# Button_Sequencer.net
KiCad netlist of a schematic drawn in EAGLE
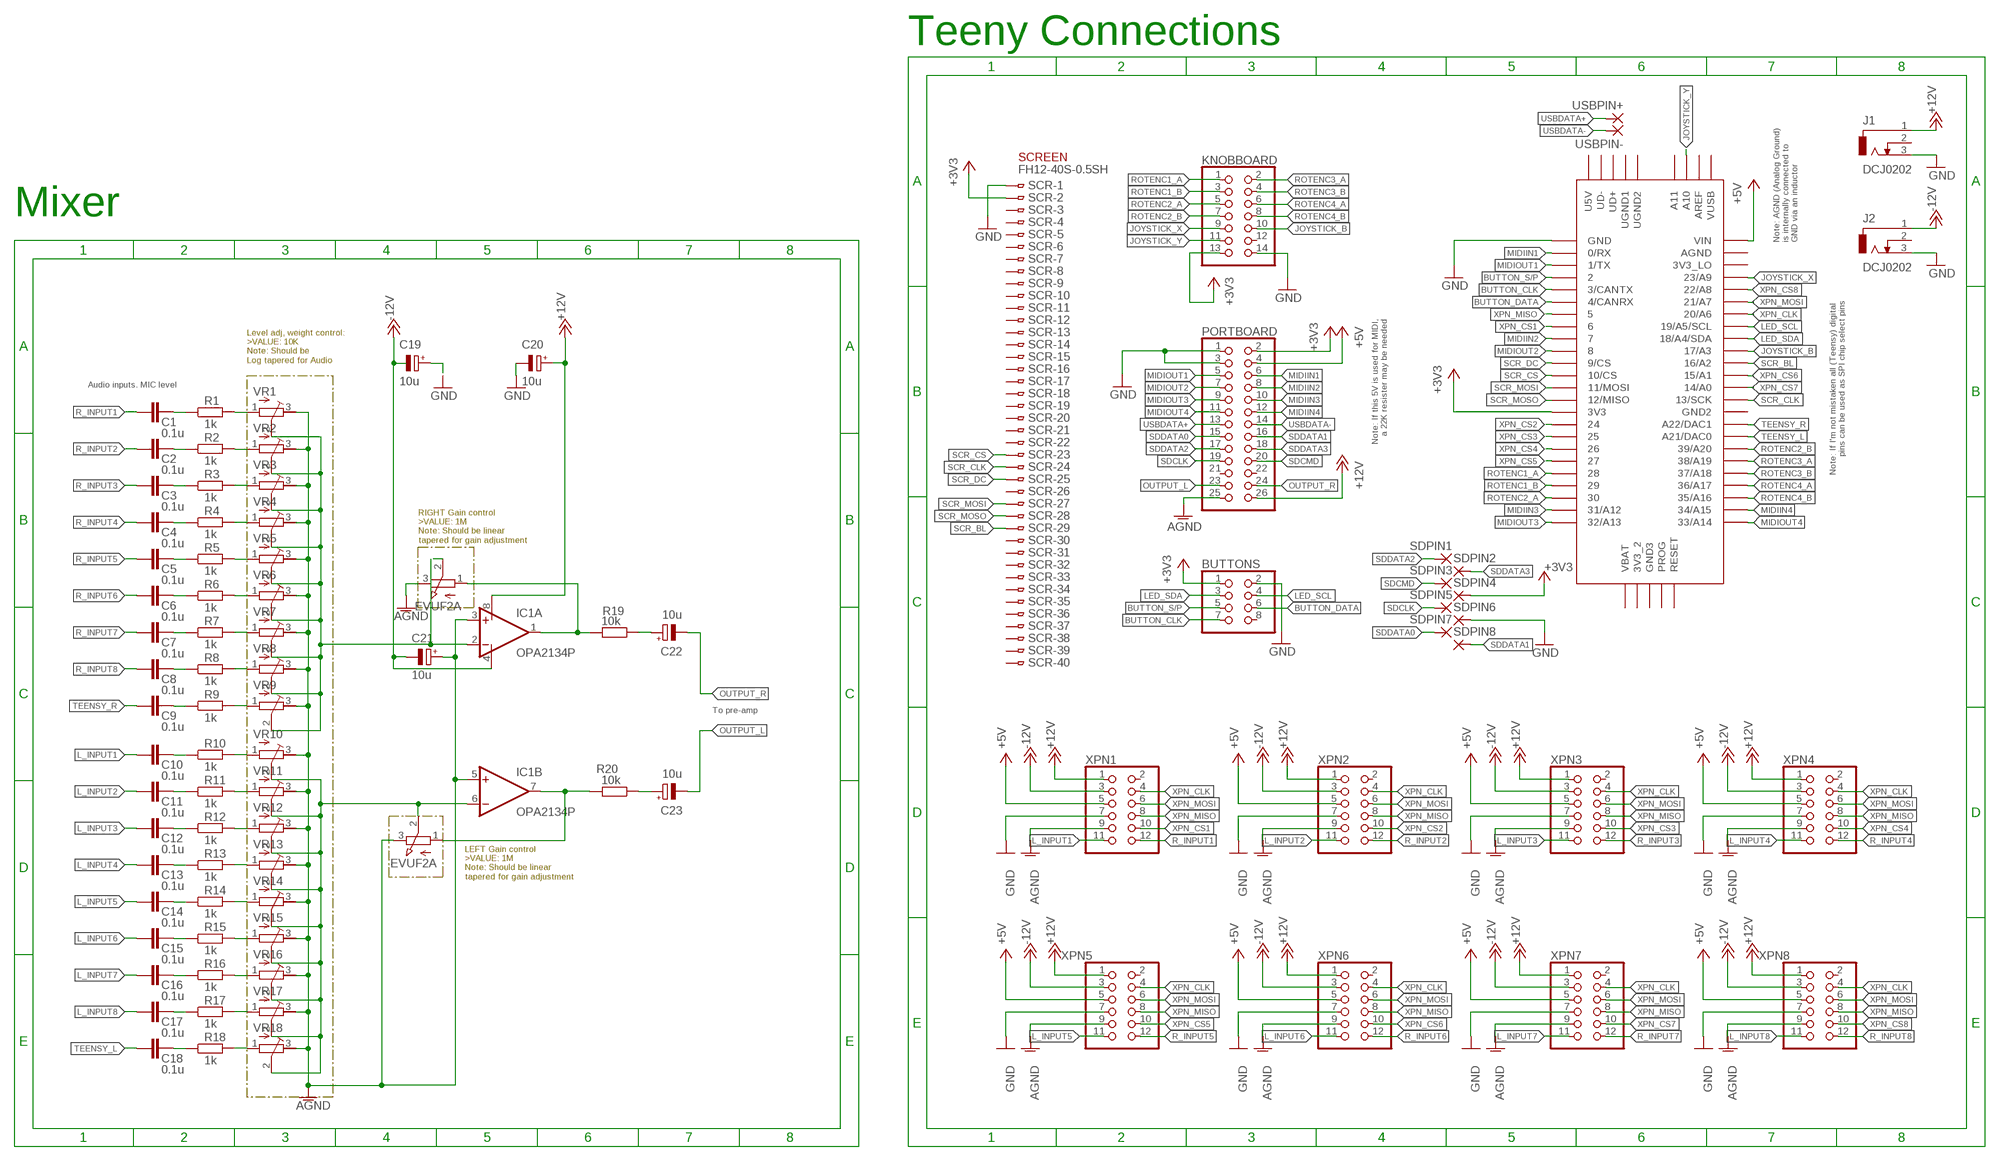
[diagram p0: schematic, sheet 1]

(export (version "E")
  (design (tool "Eeschema 10.0.6"))
  (components
    (comp (ref "BUTTONS")
      (value "PINHD-2X4")
      (footprint "eagle-import:2X04")
      (libsource (lib "eagle-import") (part "PINHD-2X4"))
    )
    (comp (ref "C1")
      (value "0.1u")
      (footprint "eagle-import:C025-030X050")
      (libsource (lib "eagle-import") (part "C-EU025-030X050"))
    )
    (comp (ref "C2")
      (value "0.1u")
      (footprint "eagle-import:C025-030X050")
      (libsource (lib "eagle-import") (part "C-EU025-030X050"))
    )
    (comp (ref "C3")
      (value "0.1u")
      (footprint "eagle-import:C025-030X050")
      (libsource (lib "eagle-import") (part "C-EU025-030X050"))
    )
    (comp (ref "C4")
      (value "0.1u")
      (footprint "eagle-import:C025-030X050")
      (libsource (lib "eagle-import") (part "C-EU025-030X050"))
    )
    (comp (ref "C5")
      (value "0.1u")
      (footprint "eagle-import:C025-030X050")
      (libsource (lib "eagle-import") (part "C-EU025-030X050"))
    )
    (comp (ref "C6")
      (value "0.1u")
      (footprint "eagle-import:C025-030X050")
      (libsource (lib "eagle-import") (part "C-EU025-030X050"))
    )
    (comp (ref "C7")
      (value "0.1u")
      (footprint "eagle-import:C025-030X050")
      (libsource (lib "eagle-import") (part "C-EU025-030X050"))
    )
    (comp (ref "C8")
      (value "0.1u")
      (footprint "eagle-import:C025-030X050")
      (libsource (lib "eagle-import") (part "C-EU025-030X050"))
    )
    (comp (ref "C9")
      (value "0.1u")
      (footprint "eagle-import:C025-030X050")
      (libsource (lib "eagle-import") (part "C-EU025-030X050"))
    )
    (comp (ref "C10")
      (value "0.1u")
      (footprint "eagle-import:C025-030X050")
      (libsource (lib "eagle-import") (part "C-EU025-030X050"))
    )
    (comp (ref "C11")
      (value "0.1u")
      (footprint "eagle-import:C025-030X050")
      (libsource (lib "eagle-import") (part "C-EU025-030X050"))
    )
    (comp (ref "C12")
      (value "0.1u")
      (footprint "eagle-import:C025-030X050")
      (libsource (lib "eagle-import") (part "C-EU025-030X050"))
    )
    (comp (ref "C13")
      (value "0.1u")
      (footprint "eagle-import:C025-030X050")
      (libsource (lib "eagle-import") (part "C-EU025-030X050"))
    )
    (comp (ref "C14")
      (value "0.1u")
      (footprint "eagle-import:C025-030X050")
      (libsource (lib "eagle-import") (part "C-EU025-030X050"))
    )
    (comp (ref "C15")
      (value "0.1u")
      (footprint "eagle-import:C025-030X050")
      (libsource (lib "eagle-import") (part "C-EU025-030X050"))
    )
    (comp (ref "C16")
      (value "0.1u")
      (footprint "eagle-import:C025-030X050")
      (libsource (lib "eagle-import") (part "C-EU025-030X050"))
    )
    (comp (ref "C17")
      (value "0.1u")
      (footprint "eagle-import:C025-030X050")
      (libsource (lib "eagle-import") (part "C-EU025-030X050"))
    )
    (comp (ref "C18")
      (value "0.1u")
      (footprint "eagle-import:C025-030X050")
      (libsource (lib "eagle-import") (part "C-EU025-030X050"))
    )
    (comp (ref "C19")
      (value "10u")
      (footprint "eagle-import:E5-10,5")
      (libsource (lib "eagle-import") (part "CPOL-EUE5-10.5"))
    )
    (comp (ref "C20")
      (value "10u")
      (footprint "eagle-import:E5-10,5")
      (libsource (lib "eagle-import") (part "CPOL-EUE5-10.5"))
    )
    (comp (ref "C21")
      (value "10u")
      (footprint "eagle-import:E5-10,5")
      (libsource (lib "eagle-import") (part "CPOL-EUE5-10.5"))
    )
    (comp (ref "C22")
      (value "10u")
      (footprint "eagle-import:E5-10,5")
      (libsource (lib "eagle-import") (part "CPOL-EUE5-10.5"))
    )
    (comp (ref "C23")
      (value "10u")
      (footprint "eagle-import:E5-10,5")
      (libsource (lib "eagle-import") (part "CPOL-EUE5-10.5"))
    )
    (comp (ref "IC1")
      (value "OPA2134P")
      (footprint "eagle-import:DIL08")
      (libsource (lib "eagle-import") (part "OPA2134P"))
    )
    (comp (ref "J1")
      (value "DCJ0202")
      (footprint "eagle-import:DCJ0202")
      (libsource (lib "eagle-import") (part "DCJ0202"))
    )
    (comp (ref "J2")
      (value "DCJ0202")
      (footprint "eagle-import:DCJ0202")
      (libsource (lib "eagle-import") (part "DCJ0202"))
    )
    (comp (ref "KNOBBOARD")
      (value "PINHD-2X7")
      (footprint "eagle-import:2X07")
      (libsource (lib "eagle-import") (part "PINHD-2X7"))
    )
    (comp (ref "PORTBOARD")
      (value "PINHD-2X13")
      (footprint "eagle-import:2X13")
      (libsource (lib "eagle-import") (part "PINHD-2X13"))
    )
    (comp (ref "R1")
      (value "1k")
      (footprint "eagle-import:R0805")
      (libsource (lib "eagle-import") (part "R-EU_R0805"))
    )
    (comp (ref "R2")
      (value "1k")
      (footprint "eagle-import:R0805")
      (libsource (lib "eagle-import") (part "R-EU_R0805"))
    )
    (comp (ref "R3")
      (value "1k")
      (footprint "eagle-import:R0805")
      (libsource (lib "eagle-import") (part "R-EU_R0805"))
    )
    (comp (ref "R4")
      (value "1k")
      (footprint "eagle-import:R0805")
      (libsource (lib "eagle-import") (part "R-EU_R0805"))
    )
    (comp (ref "R5")
      (value "1k")
      (footprint "eagle-import:R0805")
      (libsource (lib "eagle-import") (part "R-EU_R0805"))
    )
    (comp (ref "R6")
      (value "1k")
      (footprint "eagle-import:R0805")
      (libsource (lib "eagle-import") (part "R-EU_R0805"))
    )
    (comp (ref "R7")
      (value "1k")
      (footprint "eagle-import:R0805")
      (libsource (lib "eagle-import") (part "R-EU_R0805"))
    )
    (comp (ref "R8")
      (value "1k")
      (footprint "eagle-import:R0805")
      (libsource (lib "eagle-import") (part "R-EU_R0805"))
    )
    (comp (ref "R9")
      (value "1k")
      (footprint "eagle-import:R0805")
      (libsource (lib "eagle-import") (part "R-EU_R0805"))
    )
    (comp (ref "R10")
      (value "1k")
      (footprint "eagle-import:R0805")
      (libsource (lib "eagle-import") (part "R-EU_R0805"))
    )
    (comp (ref "R11")
      (value "1k")
      (footprint "eagle-import:R0805")
      (libsource (lib "eagle-import") (part "R-EU_R0805"))
    )
    (comp (ref "R12")
      (value "1k")
      (footprint "eagle-import:R0805")
      (libsource (lib "eagle-import") (part "R-EU_R0805"))
    )
    (comp (ref "R13")
      (value "1k")
      (footprint "eagle-import:R0805")
      (libsource (lib "eagle-import") (part "R-EU_R0805"))
    )
    (comp (ref "R14")
      (value "1k")
      (footprint "eagle-import:R0805")
      (libsource (lib "eagle-import") (part "R-EU_R0805"))
    )
    (comp (ref "R15")
      (value "1k")
      (footprint "eagle-import:R0805")
      (libsource (lib "eagle-import") (part "R-EU_R0805"))
    )
    (comp (ref "R16")
      (value "1k")
      (footprint "eagle-import:R0805")
      (libsource (lib "eagle-import") (part "R-EU_R0805"))
    )
    (comp (ref "R17")
      (value "1k")
      (footprint "eagle-import:R0805")
      (libsource (lib "eagle-import") (part "R-EU_R0805"))
    )
    (comp (ref "R18")
      (value "1k")
      (footprint "eagle-import:R0805")
      (libsource (lib "eagle-import") (part "R-EU_R0805"))
    )
    (comp (ref "R19")
      (value "10k")
      (footprint "eagle-import:R0805")
      (libsource (lib "eagle-import") (part "R-EU_R0805"))
    )
    (comp (ref "R20")
      (value "10k")
      (footprint "eagle-import:R0805")
      (libsource (lib "eagle-import") (part "R-EU_R0805"))
    )
    (comp (ref "SCR")
      (value "FH12-40S-0.5SH")
      (footprint "eagle-import:FH12-40S-0.5SH")
      (fields (field (name "MPN") "FH12-40S-0.5SH(55)"))
      (libsource (lib "eagle-import") (part "FH12-40S-0.5SH"))
    )
    (comp (ref "SDPIN1")
      (value "1,6/0,8")
      (footprint "eagle-import:1,6_0,8")
      (libsource (lib "eagle-import") (part "1,6/0,8"))
    )
    (comp (ref "SDPIN2")
      (value "1,6/0,8")
      (footprint "eagle-import:1,6_0,8")
      (libsource (lib "eagle-import") (part "1,6/0,8"))
    )
    (comp (ref "SDPIN3")
      (value "1,6/0,8")
      (footprint "eagle-import:1,6_0,8")
      (libsource (lib "eagle-import") (part "1,6/0,8"))
    )
    (comp (ref "SDPIN4")
      (value "1,6/0,8")
      (footprint "eagle-import:1,6_0,8")
      (libsource (lib "eagle-import") (part "1,6/0,8"))
    )
    (comp (ref "SDPIN5")
      (value "1,6/0,8")
      (footprint "eagle-import:1,6_0,8")
      (libsource (lib "eagle-import") (part "1,6/0,8"))
    )
    (comp (ref "SDPIN6")
      (value "1,6/0,8")
      (footprint "eagle-import:1,6_0,8")
      (libsource (lib "eagle-import") (part "1,6/0,8"))
    )
    (comp (ref "SDPIN7")
      (value "1,6/0,8")
      (footprint "eagle-import:1,6_0,8")
      (libsource (lib "eagle-import") (part "1,6/0,8"))
    )
    (comp (ref "SDPIN8")
      (value "1,6/0,8")
      (footprint "eagle-import:1,6_0,8")
      (libsource (lib "eagle-import") (part "1,6/0,8"))
    )
    (comp (ref "TEENSY_3.6")
      (value "TEENSY_3.5/3.6")
      (footprint "eagle-import:TEENSY_3.5_3.6")
      (libsource (lib "eagle-import") (part "TEENSY_3.5/3.6"))
    )
    (comp (ref "USBPIN+")
      (value "1,6/0,8")
      (footprint "eagle-import:1,6_0,8")
      (libsource (lib "eagle-import") (part "1,6/0,8"))
    )
    (comp (ref "USBPIN-")
      (value "1,6/0,8")
      (footprint "eagle-import:1,6_0,8")
      (libsource (lib "eagle-import") (part "1,6/0,8"))
    )
    (comp (ref "VR1")
      (value "R-TRIMM3339P")
      (footprint "eagle-import:RTRIM3339P")
      (libsource (lib "eagle-import") (part "R-TRIMM3339P"))
    )
    (comp (ref "VR2")
      (value "R-TRIMM3339P")
      (footprint "eagle-import:RTRIM3339P")
      (libsource (lib "eagle-import") (part "R-TRIMM3339P"))
    )
    (comp (ref "VR3")
      (value "R-TRIMM3339P")
      (footprint "eagle-import:RTRIM3339P")
      (libsource (lib "eagle-import") (part "R-TRIMM3339P"))
    )
    (comp (ref "VR4")
      (value "R-TRIMM3339P")
      (footprint "eagle-import:RTRIM3339P")
      (libsource (lib "eagle-import") (part "R-TRIMM3339P"))
    )
    (comp (ref "VR5")
      (value "R-TRIMM3339P")
      (footprint "eagle-import:RTRIM3339P")
      (libsource (lib "eagle-import") (part "R-TRIMM3339P"))
    )
    (comp (ref "VR6")
      (value "R-TRIMM3339P")
      (footprint "eagle-import:RTRIM3339P")
      (libsource (lib "eagle-import") (part "R-TRIMM3339P"))
    )
    (comp (ref "VR7")
      (value "R-TRIMM3339P")
      (footprint "eagle-import:RTRIM3339P")
      (libsource (lib "eagle-import") (part "R-TRIMM3339P"))
    )
    (comp (ref "VR8")
      (value "R-TRIMM3339P")
      (footprint "eagle-import:RTRIM3339P")
      (libsource (lib "eagle-import") (part "R-TRIMM3339P"))
    )
    (comp (ref "VR9")
      (value "R-TRIMM3339P")
      (footprint "eagle-import:RTRIM3339P")
      (libsource (lib "eagle-import") (part "R-TRIMM3339P"))
    )
    (comp (ref "VR10")
      (value "R-TRIMM3339P")
      (footprint "eagle-import:RTRIM3339P")
      (libsource (lib "eagle-import") (part "R-TRIMM3339P"))
    )
    (comp (ref "VR11")
      (value "R-TRIMM3339P")
      (footprint "eagle-import:RTRIM3339P")
      (libsource (lib "eagle-import") (part "R-TRIMM3339P"))
    )
    (comp (ref "VR12")
      (value "R-TRIMM3339P")
      (footprint "eagle-import:RTRIM3339P")
      (libsource (lib "eagle-import") (part "R-TRIMM3339P"))
    )
    (comp (ref "VR13")
      (value "R-TRIMM3339P")
      (footprint "eagle-import:RTRIM3339P")
      (libsource (lib "eagle-import") (part "R-TRIMM3339P"))
    )
    (comp (ref "VR14")
      (value "R-TRIMM3339P")
      (footprint "eagle-import:RTRIM3339P")
      (libsource (lib "eagle-import") (part "R-TRIMM3339P"))
    )
    (comp (ref "VR15")
      (value "R-TRIMM3339P")
      (footprint "eagle-import:RTRIM3339P")
      (libsource (lib "eagle-import") (part "R-TRIMM3339P"))
    )
    (comp (ref "VR16")
      (value "R-TRIMM3339P")
      (footprint "eagle-import:RTRIM3339P")
      (libsource (lib "eagle-import") (part "R-TRIMM3339P"))
    )
    (comp (ref "VR17")
      (value "R-TRIMM3339P")
      (footprint "eagle-import:RTRIM3339P")
      (libsource (lib "eagle-import") (part "R-TRIMM3339P"))
    )
    (comp (ref "VR18")
      (value "R-TRIMM3339P")
      (footprint "eagle-import:RTRIM3339P")
      (libsource (lib "eagle-import") (part "R-TRIMM3339P"))
    )
    (comp (ref "VR19")
      (value "EVUF2A")
      (footprint "eagle-import:EVUF")
      (libsource (lib "eagle-import") (part "EVUAF2"))
    )
    (comp (ref "VR20")
      (value "EVUF2A")
      (footprint "eagle-import:EVUF")
      (libsource (lib "eagle-import") (part "EVUAF2"))
    )
    (comp (ref "XPN1")
      (value "PINHD-2X6")
      (footprint "eagle-import:2X06")
      (libsource (lib "eagle-import") (part "PINHD-2X6"))
    )
    (comp (ref "XPN2")
      (value "PINHD-2X6")
      (footprint "eagle-import:2X06")
      (libsource (lib "eagle-import") (part "PINHD-2X6"))
    )
    (comp (ref "XPN3")
      (value "PINHD-2X6")
      (footprint "eagle-import:2X06")
      (libsource (lib "eagle-import") (part "PINHD-2X6"))
    )
    (comp (ref "XPN4")
      (value "PINHD-2X6")
      (footprint "eagle-import:2X06")
      (libsource (lib "eagle-import") (part "PINHD-2X6"))
    )
    (comp (ref "XPN5")
      (value "PINHD-2X6")
      (footprint "eagle-import:2X06")
      (libsource (lib "eagle-import") (part "PINHD-2X6"))
    )
    (comp (ref "XPN6")
      (value "PINHD-2X6")
      (footprint "eagle-import:2X06")
      (libsource (lib "eagle-import") (part "PINHD-2X6"))
    )
    (comp (ref "XPN7")
      (value "PINHD-2X6")
      (footprint "eagle-import:2X06")
      (libsource (lib "eagle-import") (part "PINHD-2X6"))
    )
    (comp (ref "XPN8")
      (value "PINHD-2X6")
      (footprint "eagle-import:2X06")
      (libsource (lib "eagle-import") (part "PINHD-2X6"))
    )
  )
  (nets
    (net (code "1") (name "+3V3") (class "Default")
      (node (ref "BUTTONS") (pin "1") (pinfunction "1_1") (pintype "passive"))
      (node (ref "KNOBBOARD") (pin "13") (pinfunction "13_13") (pintype "passive"))
      (node (ref "PORTBOARD") (pin "2") (pinfunction "2_2") (pintype "passive"))
      (node (ref "SCR") (pin "2") (pinfunction "1_2") (pintype "passive"))
      (node (ref "SDPIN4") (pin "1") (pinfunction "P_1") (pintype "passive"))
      (node (ref "TEENSY_3.6") (pin "3V3") (pinfunction "3V3_3V3") (pintype "bidirectional"))
    )
    (net (code "2") (name "+5V") (class "Default")
      (node (ref "PORTBOARD") (pin "4") (pinfunction "4_4") (pintype "passive"))
      (node (ref "TEENSY_3.6") (pin "VIN") (pinfunction "VIN_VIN") (pintype "bidirectional"))
      (node (ref "XPN1") (pin "5") (pinfunction "5_5") (pintype "passive"))
      (node (ref "XPN2") (pin "5") (pinfunction "5_5") (pintype "passive"))
      (node (ref "XPN3") (pin "5") (pinfunction "5_5") (pintype "passive"))
      (node (ref "XPN4") (pin "5") (pinfunction "5_5") (pintype "passive"))
      (node (ref "XPN5") (pin "5") (pinfunction "5_5") (pintype "passive"))
      (node (ref "XPN6") (pin "5") (pinfunction "5_5") (pintype "passive"))
      (node (ref "XPN7") (pin "5") (pinfunction "5_5") (pintype "passive"))
      (node (ref "XPN8") (pin "5") (pinfunction "5_5") (pintype "passive"))
    )
    (net (code "3") (name "+12V") (class "Default")
      (node (ref "C20") (pin "+") (pinfunction "+_+") (pintype "passive"))
      (node (ref "IC1") (pin "8") (pinfunction "V+_8") (pintype "power_in"))
      (node (ref "J1") (pin "1") (pinfunction "1_1") (pintype "passive"))
      (node (ref "PORTBOARD") (pin "26") (pinfunction "26_26") (pintype "passive"))
      (node (ref "XPN1") (pin "1") (pinfunction "1_1") (pintype "passive"))
      (node (ref "XPN2") (pin "1") (pinfunction "1_1") (pintype "passive"))
      (node (ref "XPN3") (pin "1") (pinfunction "1_1") (pintype "passive"))
      (node (ref "XPN4") (pin "1") (pinfunction "1_1") (pintype "passive"))
      (node (ref "XPN5") (pin "1") (pinfunction "1_1") (pintype "passive"))
      (node (ref "XPN6") (pin "1") (pinfunction "1_1") (pintype "passive"))
      (node (ref "XPN7") (pin "1") (pinfunction "1_1") (pintype "passive"))
      (node (ref "XPN8") (pin "1") (pinfunction "1_1") (pintype "passive"))
    )
    (net (code "4") (name "-12V") (class "Default")
      (node (ref "C19") (pin "-") (pinfunction "-_-") (pintype "passive"))
      (node (ref "C21") (pin "-") (pinfunction "-_-") (pintype "passive"))
      (node (ref "IC1") (pin "4") (pinfunction "V-_4") (pintype "power_in"))
      (node (ref "J2") (pin "1") (pinfunction "1_1") (pintype "passive"))
      (node (ref "XPN1") (pin "3") (pinfunction "3_3") (pintype "passive"))
      (node (ref "XPN2") (pin "3") (pinfunction "3_3") (pintype "passive"))
      (node (ref "XPN3") (pin "3") (pinfunction "3_3") (pintype "passive"))
      (node (ref "XPN4") (pin "3") (pinfunction "3_3") (pintype "passive"))
      (node (ref "XPN5") (pin "3") (pinfunction "3_3") (pintype "passive"))
      (node (ref "XPN6") (pin "3") (pinfunction "3_3") (pintype "passive"))
      (node (ref "XPN7") (pin "3") (pinfunction "3_3") (pintype "passive"))
      (node (ref "XPN8") (pin "3") (pinfunction "3_3") (pintype "passive"))
    )
    (net (code "5") (name "AGND") (class "Default")
      (node (ref "C21") (pin "+") (pinfunction "+_+") (pintype "passive"))
      (node (ref "IC1") (pin "3") (pinfunction "+IN_3") (pintype "input"))
      (node (ref "IC1") (pin "5") (pinfunction "+IN_5") (pintype "input"))
      (node (ref "PORTBOARD") (pin "25") (pinfunction "25_25") (pintype "passive"))
      (node (ref "VR1") (pin "3") (pinfunction "E_3") (pintype "passive"))
      (node (ref "VR10") (pin "3") (pinfunction "E_3") (pintype "passive"))
      (node (ref "VR11") (pin "3") (pinfunction "E_3") (pintype "passive"))
      (node (ref "VR12") (pin "3") (pinfunction "E_3") (pintype "passive"))
      (node (ref "VR13") (pin "3") (pinfunction "E_3") (pintype "passive"))
      (node (ref "VR14") (pin "3") (pinfunction "E_3") (pintype "passive"))
      (node (ref "VR15") (pin "3") (pinfunction "E_3") (pintype "passive"))
      (node (ref "VR16") (pin "3") (pinfunction "E_3") (pintype "passive"))
      (node (ref "VR17") (pin "3") (pinfunction "E_3") (pintype "passive"))
      (node (ref "VR18") (pin "3") (pinfunction "E_3") (pintype "passive"))
      (node (ref "VR19") (pin "3") (pinfunction "E_3") (pintype "passive"))
      (node (ref "VR2") (pin "3") (pinfunction "E_3") (pintype "passive"))
      (node (ref "VR20") (pin "3") (pinfunction "E_3") (pintype "passive"))
      (node (ref "VR3") (pin "3") (pinfunction "E_3") (pintype "passive"))
      (node (ref "VR4") (pin "3") (pinfunction "E_3") (pintype "passive"))
      (node (ref "VR5") (pin "3") (pinfunction "E_3") (pintype "passive"))
      (node (ref "VR6") (pin "3") (pinfunction "E_3") (pintype "passive"))
      (node (ref "VR7") (pin "3") (pinfunction "E_3") (pintype "passive"))
      (node (ref "VR8") (pin "3") (pinfunction "E_3") (pintype "passive"))
      (node (ref "VR9") (pin "3") (pinfunction "E_3") (pintype "passive"))
      (node (ref "XPN1") (pin "9") (pinfunction "9_9") (pintype "passive"))
      (node (ref "XPN2") (pin "9") (pinfunction "9_9") (pintype "passive"))
      (node (ref "XPN3") (pin "9") (pinfunction "9_9") (pintype "passive"))
      (node (ref "XPN4") (pin "9") (pinfunction "9_9") (pintype "passive"))
      (node (ref "XPN5") (pin "9") (pinfunction "9_9") (pintype "passive"))
      (node (ref "XPN6") (pin "9") (pinfunction "9_9") (pintype "passive"))
      (node (ref "XPN7") (pin "9") (pinfunction "9_9") (pintype "passive"))
      (node (ref "XPN8") (pin "9") (pinfunction "9_9") (pintype "passive"))
    )
    (net (code "6") (name "BUTTON_CLK") (class "Default")
      (node (ref "BUTTONS") (pin "7") (pinfunction "7_7") (pintype "passive"))
      (node (ref "TEENSY_3.6") (pin "3/CANTX") (pinfunction "3/CANTX_3/CANTX") (pintype "bidirectional"))
    )
    (net (code "7") (name "BUTTON_DATA") (class "Default")
      (node (ref "BUTTONS") (pin "6") (pinfunction "6_6") (pintype "passive"))
      (node (ref "TEENSY_3.6") (pin "4/CANRX") (pinfunction "4/CANRX_4/CANRX") (pintype "bidirectional"))
    )
    (net (code "8") (name "BUTTON_S{slash}P") (class "Default")
      (node (ref "BUTTONS") (pin "5") (pinfunction "5_5") (pintype "passive"))
      (node (ref "TEENSY_3.6") (pin "2") (pinfunction "2_2") (pintype "bidirectional"))
    )
    (net (code "9") (name "GND") (class "Default")
      (node (ref "BUTTONS") (pin "2") (pinfunction "2_2") (pintype "passive"))
      (node (ref "C19") (pin "+") (pinfunction "+_+") (pintype "passive"))
      (node (ref "C20") (pin "-") (pinfunction "-_-") (pintype "passive"))
      (node (ref "J1") (pin "3") (pinfunction "3_3") (pintype "passive"))
      (node (ref "J2") (pin "3") (pinfunction "3_3") (pintype "passive"))
      (node (ref "KNOBBOARD") (pin "14") (pinfunction "14_14") (pintype "passive"))
      (node (ref "PORTBOARD") (pin "1") (pinfunction "1_1") (pintype "passive"))
      (node (ref "PORTBOARD") (pin "3") (pinfunction "3_3") (pintype "passive"))
      (node (ref "SCR") (pin "1") (pinfunction "1_1") (pintype "passive"))
      (node (ref "SDPIN6") (pin "1") (pinfunction "P_1") (pintype "passive"))
      (node (ref "TEENSY_3.6") (pin "GND") (pinfunction "GND_GND") (pintype "bidirectional"))
      (node (ref "XPN1") (pin "7") (pinfunction "7_7") (pintype "passive"))
      (node (ref "XPN2") (pin "7") (pinfunction "7_7") (pintype "passive"))
      (node (ref "XPN3") (pin "7") (pinfunction "7_7") (pintype "passive"))
      (node (ref "XPN4") (pin "7") (pinfunction "7_7") (pintype "passive"))
      (node (ref "XPN5") (pin "7") (pinfunction "7_7") (pintype "passive"))
      (node (ref "XPN6") (pin "7") (pinfunction "7_7") (pintype "passive"))
      (node (ref "XPN7") (pin "7") (pinfunction "7_7") (pintype "passive"))
      (node (ref "XPN8") (pin "7") (pinfunction "7_7") (pintype "passive"))
    )
    (net (code "10") (name "JOYSTICK_B") (class "Default")
      (node (ref "KNOBBOARD") (pin "10") (pinfunction "10_10") (pintype "passive"))
      (node (ref "TEENSY_3.6") (pin "17/A3") (pinfunction "17/A3_17/A3") (pintype "bidirectional"))
    )
    (net (code "11") (name "JOYSTICK_X") (class "Default")
      (node (ref "KNOBBOARD") (pin "9") (pinfunction "9_9") (pintype "passive"))
      (node (ref "TEENSY_3.6") (pin "23/A9") (pinfunction "23/A9_23/A9") (pintype "bidirectional"))
    )
    (net (code "12") (name "JOYSTICK_Y") (class "Default")
      (node (ref "KNOBBOARD") (pin "11") (pinfunction "11_11") (pintype "passive"))
      (node (ref "TEENSY_3.6") (pin "A10") (pinfunction "A10_A10") (pintype "bidirectional"))
    )
    (net (code "13") (name "LED_SCL") (class "Default")
      (node (ref "BUTTONS") (pin "4") (pinfunction "4_4") (pintype "passive"))
      (node (ref "TEENSY_3.6") (pin "19/A5/SCL") (pinfunction "19/A5/SCL_19/A5/SCL") (pintype "bidirectional"))
    )
    (net (code "14") (name "LED_SDA") (class "Default")
      (node (ref "BUTTONS") (pin "3") (pinfunction "3_3") (pintype "passive"))
      (node (ref "TEENSY_3.6") (pin "18/A4/SDA") (pinfunction "18/A4/SDA_18/A4/SDA") (pintype "bidirectional"))
    )
    (net (code "15") (name "L_INPUT1") (class "Default")
      (node (ref "C10") (pin "2") (pinfunction "2_2") (pintype "passive"))
      (node (ref "XPN1") (pin "11") (pinfunction "11_11") (pintype "passive"))
    )
    (net (code "16") (name "L_INPUT2") (class "Default")
      (node (ref "C11") (pin "2") (pinfunction "2_2") (pintype "passive"))
      (node (ref "XPN2") (pin "11") (pinfunction "11_11") (pintype "passive"))
    )
    (net (code "17") (name "L_INPUT3") (class "Default")
      (node (ref "C12") (pin "2") (pinfunction "2_2") (pintype "passive"))
      (node (ref "XPN3") (pin "11") (pinfunction "11_11") (pintype "passive"))
    )
    (net (code "18") (name "L_INPUT4") (class "Default")
      (node (ref "C13") (pin "2") (pinfunction "2_2") (pintype "passive"))
      (node (ref "XPN4") (pin "11") (pinfunction "11_11") (pintype "passive"))
    )
    (net (code "19") (name "L_INPUT5") (class "Default")
      (node (ref "C14") (pin "2") (pinfunction "2_2") (pintype "passive"))
      (node (ref "XPN5") (pin "11") (pinfunction "11_11") (pintype "passive"))
    )
    (net (code "20") (name "L_INPUT6") (class "Default")
      (node (ref "C15") (pin "2") (pinfunction "2_2") (pintype "passive"))
      (node (ref "XPN6") (pin "11") (pinfunction "11_11") (pintype "passive"))
    )
    (net (code "21") (name "L_INPUT7") (class "Default")
      (node (ref "C16") (pin "2") (pinfunction "2_2") (pintype "passive"))
      (node (ref "XPN7") (pin "11") (pinfunction "11_11") (pintype "passive"))
    )
    (net (code "22") (name "L_INPUT8") (class "Default")
      (node (ref "C17") (pin "2") (pinfunction "2_2") (pintype "passive"))
      (node (ref "XPN8") (pin "11") (pinfunction "11_11") (pintype "passive"))
    )
    (net (code "23") (name "MIDIIN1") (class "Default")
      (node (ref "PORTBOARD") (pin "6") (pinfunction "6_6") (pintype "passive"))
      (node (ref "TEENSY_3.6") (pin "0/RX") (pinfunction "0/RX_0/RX") (pintype "bidirectional"))
    )
    (net (code "24") (name "MIDIIN2") (class "Default")
      (node (ref "PORTBOARD") (pin "8") (pinfunction "8_8") (pintype "passive"))
      (node (ref "TEENSY_3.6") (pin "7") (pinfunction "7_7") (pintype "bidirectional"))
    )
    (net (code "25") (name "MIDIIN3") (class "Default")
      (node (ref "PORTBOARD") (pin "10") (pinfunction "10_10") (pintype "passive"))
      (node (ref "TEENSY_3.6") (pin "31/A12") (pinfunction "31/A12_31/A12") (pintype "bidirectional"))
    )
    (net (code "26") (name "MIDIIN4") (class "Default")
      (node (ref "PORTBOARD") (pin "12") (pinfunction "12_12") (pintype "passive"))
      (node (ref "TEENSY_3.6") (pin "34/A15") (pinfunction "34/A15_34/A15") (pintype "bidirectional"))
    )
    (net (code "27") (name "MIDIOUT1") (class "Default")
      (node (ref "PORTBOARD") (pin "5") (pinfunction "5_5") (pintype "passive"))
      (node (ref "TEENSY_3.6") (pin "1/TX") (pinfunction "1/TX_1/TX") (pintype "bidirectional"))
    )
    (net (code "28") (name "MIDIOUT2") (class "Default")
      (node (ref "PORTBOARD") (pin "7") (pinfunction "7_7") (pintype "passive"))
      (node (ref "TEENSY_3.6") (pin "8") (pinfunction "8_8") (pintype "bidirectional"))
    )
    (net (code "29") (name "MIDIOUT3") (class "Default")
      (node (ref "PORTBOARD") (pin "9") (pinfunction "9_9") (pintype "passive"))
      (node (ref "TEENSY_3.6") (pin "32/A13") (pinfunction "32/A13_32/A13") (pintype "bidirectional"))
    )
    (net (code "30") (name "MIDIOUT4") (class "Default")
      (node (ref "PORTBOARD") (pin "11") (pinfunction "11_11") (pintype "passive"))
      (node (ref "TEENSY_3.6") (pin "33/A14") (pinfunction "33/A14_33/A14") (pintype "bidirectional"))
    )
    (net (code "31") (name "Net-(C1-Pad1)") (class "Default")
      (node (ref "C1") (pin "1") (pinfunction "1_1") (pintype "passive"))
      (node (ref "R1") (pin "1") (pinfunction "1_1") (pintype "passive"))
    )
    (net (code "32") (name "Net-(C2-Pad1)") (class "Default")
      (node (ref "C2") (pin "1") (pinfunction "1_1") (pintype "passive"))
      (node (ref "R2") (pin "1") (pinfunction "1_1") (pintype "passive"))
    )
    (net (code "33") (name "Net-(C3-Pad1)") (class "Default")
      (node (ref "C3") (pin "1") (pinfunction "1_1") (pintype "passive"))
      (node (ref "R3") (pin "1") (pinfunction "1_1") (pintype "passive"))
    )
    (net (code "34") (name "Net-(C4-Pad1)") (class "Default")
      (node (ref "C4") (pin "1") (pinfunction "1_1") (pintype "passive"))
      (node (ref "R4") (pin "1") (pinfunction "1_1") (pintype "passive"))
    )
    (net (code "35") (name "Net-(C5-Pad1)") (class "Default")
      (node (ref "C5") (pin "1") (pinfunction "1_1") (pintype "passive"))
      (node (ref "R5") (pin "1") (pinfunction "1_1") (pintype "passive"))
    )
    (net (code "36") (name "Net-(C6-Pad1)") (class "Default")
      (node (ref "C6") (pin "1") (pinfunction "1_1") (pintype "passive"))
      (node (ref "R6") (pin "1") (pinfunction "1_1") (pintype "passive"))
    )
    (net (code "37") (name "Net-(C7-Pad1)") (class "Default")
      (node (ref "C7") (pin "1") (pinfunction "1_1") (pintype "passive"))
      (node (ref "R7") (pin "1") (pinfunction "1_1") (pintype "passive"))
    )
    (net (code "38") (name "Net-(C8-Pad1)") (class "Default")
      (node (ref "C8") (pin "1") (pinfunction "1_1") (pintype "passive"))
      (node (ref "R8") (pin "1") (pinfunction "1_1") (pintype "passive"))
    )
    (net (code "39") (name "Net-(C9-Pad1)") (class "Default")
      (node (ref "C9") (pin "1") (pinfunction "1_1") (pintype "passive"))
      (node (ref "R9") (pin "1") (pinfunction "1_1") (pintype "passive"))
    )
    (net (code "40") (name "Net-(C10-Pad1)") (class "Default")
      (node (ref "C10") (pin "1") (pinfunction "1_1") (pintype "passive"))
      (node (ref "R10") (pin "1") (pinfunction "1_1") (pintype "passive"))
    )
    (net (code "41") (name "Net-(C11-Pad1)") (class "Default")
      (node (ref "C11") (pin "1") (pinfunction "1_1") (pintype "passive"))
      (node (ref "R11") (pin "1") (pinfunction "1_1") (pintype "passive"))
    )
    (net (code "42") (name "Net-(C12-Pad1)") (class "Default")
      (node (ref "C12") (pin "1") (pinfunction "1_1") (pintype "passive"))
      (node (ref "R12") (pin "1") (pinfunction "1_1") (pintype "passive"))
    )
    (net (code "43") (name "Net-(C13-Pad1)") (class "Default")
      (node (ref "C13") (pin "1") (pinfunction "1_1") (pintype "passive"))
      (node (ref "R13") (pin "1") (pinfunction "1_1") (pintype "passive"))
    )
    (net (code "44") (name "Net-(C14-Pad1)") (class "Default")
      (node (ref "C14") (pin "1") (pinfunction "1_1") (pintype "passive"))
      (node (ref "R14") (pin "1") (pinfunction "1_1") (pintype "passive"))
    )
    (net (code "45") (name "Net-(C15-Pad1)") (class "Default")
      (node (ref "C15") (pin "1") (pinfunction "1_1") (pintype "passive"))
      (node (ref "R15") (pin "1") (pinfunction "1_1") (pintype "passive"))
    )
    (net (code "46") (name "Net-(C16-Pad1)") (class "Default")
      (node (ref "C16") (pin "1") (pinfunction "1_1") (pintype "passive"))
      (node (ref "R16") (pin "1") (pinfunction "1_1") (pintype "passive"))
    )
    (net (code "47") (name "Net-(C17-Pad1)") (class "Default")
      (node (ref "C17") (pin "1") (pinfunction "1_1") (pintype "passive"))
      (node (ref "R17") (pin "1") (pinfunction "1_1") (pintype "passive"))
    )
    (net (code "48") (name "Net-(C18-Pad1)") (class "Default")
      (node (ref "C18") (pin "1") (pinfunction "1_1") (pintype "passive"))
      (node (ref "R18") (pin "1") (pinfunction "1_1") (pintype "passive"))
    )
    (net (code "49") (name "Net-(C22-Pad+)") (class "Default")
      (node (ref "C22") (pin "+") (pinfunction "+_+") (pintype "passive"))
      (node (ref "R19") (pin "1") (pinfunction "1_1") (pintype "passive"))
    )
    (net (code "50") (name "Net-(C23-Pad+)") (class "Default")
      (node (ref "C23") (pin "+") (pinfunction "+_+") (pintype "passive"))
      (node (ref "R20") (pin "1") (pinfunction "1_1") (pintype "passive"))
    )
    (net (code "51") (name "Net-(IC1A--IN)") (class "Default")
      (node (ref "IC1") (pin "2") (pinfunction "-IN_2") (pintype "input"))
      (node (ref "VR1") (pin "2") (pinfunction "S_2") (pintype "passive"))
      (node (ref "VR19") (pin "2") (pinfunction "S_2") (pintype "passive"))
      (node (ref "VR2") (pin "2") (pinfunction "S_2") (pintype "passive"))
      (node (ref "VR3") (pin "2") (pinfunction "S_2") (pintype "passive"))
      (node (ref "VR4") (pin "2") (pinfunction "S_2") (pintype "passive"))
      (node (ref "VR5") (pin "2") (pinfunction "S_2") (pintype "passive"))
      (node (ref "VR6") (pin "2") (pinfunction "S_2") (pintype "passive"))
      (node (ref "VR7") (pin "2") (pinfunction "S_2") (pintype "passive"))
      (node (ref "VR8") (pin "2") (pinfunction "S_2") (pintype "passive"))
      (node (ref "VR9") (pin "2") (pinfunction "S_2") (pintype "passive"))
    )
    (net (code "52") (name "Net-(IC1A-OUT)") (class "Default")
      (node (ref "IC1") (pin "1") (pinfunction "OUT_1") (pintype "output"))
      (node (ref "R19") (pin "2") (pinfunction "2_2") (pintype "passive"))
      (node (ref "VR19") (pin "1") (pinfunction "A_1") (pintype "passive"))
    )
    (net (code "53") (name "Net-(IC1B--IN)") (class "Default")
      (node (ref "IC1") (pin "6") (pinfunction "-IN_6") (pintype "input"))
      (node (ref "VR10") (pin "2") (pinfunction "S_2") (pintype "passive"))
      (node (ref "VR11") (pin "2") (pinfunction "S_2") (pintype "passive"))
      (node (ref "VR12") (pin "2") (pinfunction "S_2") (pintype "passive"))
      (node (ref "VR13") (pin "2") (pinfunction "S_2") (pintype "passive"))
      (node (ref "VR14") (pin "2") (pinfunction "S_2") (pintype "passive"))
      (node (ref "VR15") (pin "2") (pinfunction "S_2") (pintype "passive"))
      (node (ref "VR16") (pin "2") (pinfunction "S_2") (pintype "passive"))
      (node (ref "VR17") (pin "2") (pinfunction "S_2") (pintype "passive"))
      (node (ref "VR18") (pin "2") (pinfunction "S_2") (pintype "passive"))
      (node (ref "VR20") (pin "2") (pinfunction "S_2") (pintype "passive"))
    )
    (net (code "54") (name "Net-(IC1B-OUT)") (class "Default")
      (node (ref "IC1") (pin "7") (pinfunction "OUT_7") (pintype "output"))
      (node (ref "R20") (pin "2") (pinfunction "2_2") (pintype "passive"))
      (node (ref "VR20") (pin "1") (pinfunction "A_1") (pintype "passive"))
    )
    (net (code "55") (name "Net-(VR1-A)") (class "Default")
      (node (ref "R1") (pin "2") (pinfunction "2_2") (pintype "passive"))
      (node (ref "VR1") (pin "1") (pinfunction "A_1") (pintype "passive"))
    )
    (net (code "56") (name "Net-(VR2-A)") (class "Default")
      (node (ref "R2") (pin "2") (pinfunction "2_2") (pintype "passive"))
      (node (ref "VR2") (pin "1") (pinfunction "A_1") (pintype "passive"))
    )
    (net (code "57") (name "Net-(VR3-A)") (class "Default")
      (node (ref "R3") (pin "2") (pinfunction "2_2") (pintype "passive"))
      (node (ref "VR3") (pin "1") (pinfunction "A_1") (pintype "passive"))
    )
    (net (code "58") (name "Net-(VR4-A)") (class "Default")
      (node (ref "R4") (pin "2") (pinfunction "2_2") (pintype "passive"))
      (node (ref "VR4") (pin "1") (pinfunction "A_1") (pintype "passive"))
    )
    (net (code "59") (name "Net-(VR5-A)") (class "Default")
      (node (ref "R5") (pin "2") (pinfunction "2_2") (pintype "passive"))
      (node (ref "VR5") (pin "1") (pinfunction "A_1") (pintype "passive"))
    )
    (net (code "60") (name "Net-(VR6-A)") (class "Default")
      (node (ref "R6") (pin "2") (pinfunction "2_2") (pintype "passive"))
      (node (ref "VR6") (pin "1") (pinfunction "A_1") (pintype "passive"))
    )
    (net (code "61") (name "Net-(VR7-A)") (class "Default")
      (node (ref "R7") (pin "2") (pinfunction "2_2") (pintype "passive"))
      (node (ref "VR7") (pin "1") (pinfunction "A_1") (pintype "passive"))
    )
    (net (code "62") (name "Net-(VR8-A)") (class "Default")
      (node (ref "R8") (pin "2") (pinfunction "2_2") (pintype "passive"))
      (node (ref "VR8") (pin "1") (pinfunction "A_1") (pintype "passive"))
    )
    (net (code "63") (name "Net-(VR9-A)") (class "Default")
      (node (ref "R9") (pin "2") (pinfunction "2_2") (pintype "passive"))
      (node (ref "VR9") (pin "1") (pinfunction "A_1") (pintype "passive"))
    )
    (net (code "64") (name "Net-(VR10-A)") (class "Default")
      (node (ref "R10") (pin "2") (pinfunction "2_2") (pintype "passive"))
      (node (ref "VR10") (pin "1") (pinfunction "A_1") (pintype "passive"))
    )
    (net (code "65") (name "Net-(VR11-A)") (class "Default")
      (node (ref "R11") (pin "2") (pinfunction "2_2") (pintype "passive"))
      (node (ref "VR11") (pin "1") (pinfunction "A_1") (pintype "passive"))
    )
    (net (code "66") (name "Net-(VR12-A)") (class "Default")
      (node (ref "R12") (pin "2") (pinfunction "2_2") (pintype "passive"))
      (node (ref "VR12") (pin "1") (pinfunction "A_1") (pintype "passive"))
    )
    (net (code "67") (name "Net-(VR13-A)") (class "Default")
      (node (ref "R13") (pin "2") (pinfunction "2_2") (pintype "passive"))
      (node (ref "VR13") (pin "1") (pinfunction "A_1") (pintype "passive"))
    )
    (net (code "68") (name "Net-(VR14-A)") (class "Default")
      (node (ref "R14") (pin "2") (pinfunction "2_2") (pintype "passive"))
      (node (ref "VR14") (pin "1") (pinfunction "A_1") (pintype "passive"))
    )
    (net (code "69") (name "Net-(VR15-A)") (class "Default")
      (node (ref "R15") (pin "2") (pinfunction "2_2") (pintype "passive"))
      (node (ref "VR15") (pin "1") (pinfunction "A_1") (pintype "passive"))
    )
    (net (code "70") (name "Net-(VR16-A)") (class "Default")
      (node (ref "R16") (pin "2") (pinfunction "2_2") (pintype "passive"))
      (node (ref "VR16") (pin "1") (pinfunction "A_1") (pintype "passive"))
    )
    (net (code "71") (name "Net-(VR17-A)") (class "Default")
      (node (ref "R17") (pin "2") (pinfunction "2_2") (pintype "passive"))
      (node (ref "VR17") (pin "1") (pinfunction "A_1") (pintype "passive"))
    )
    (net (code "72") (name "Net-(VR18-A)") (class "Default")
      (node (ref "R18") (pin "2") (pinfunction "2_2") (pintype "passive"))
      (node (ref "VR18") (pin "1") (pinfunction "A_1") (pintype "passive"))
    )
    (net (code "73") (name "OUTPUT_L") (class "Default")
      (node (ref "C23") (pin "-") (pinfunction "-_-") (pintype "passive"))
      (node (ref "PORTBOARD") (pin "23") (pinfunction "23_23") (pintype "passive"))
    )
    (net (code "74") (name "OUTPUT_R") (class "Default")
      (node (ref "C22") (pin "-") (pinfunction "-_-") (pintype "passive"))
      (node (ref "PORTBOARD") (pin "24") (pinfunction "24_24") (pintype "passive"))
    )
    (net (code "75") (name "ROTENC1_A") (class "Default")
      (node (ref "KNOBBOARD") (pin "1") (pinfunction "1_1") (pintype "passive"))
      (node (ref "TEENSY_3.6") (pin "28") (pinfunction "28_28") (pintype "bidirectional"))
    )
    (net (code "76") (name "ROTENC1_B") (class "Default")
      (node (ref "KNOBBOARD") (pin "3") (pinfunction "3_3") (pintype "passive"))
      (node (ref "TEENSY_3.6") (pin "29") (pinfunction "29_29") (pintype "bidirectional"))
    )
    (net (code "77") (name "ROTENC2_A") (class "Default")
      (node (ref "KNOBBOARD") (pin "5") (pinfunction "5_5") (pintype "passive"))
      (node (ref "TEENSY_3.6") (pin "30") (pinfunction "30_30") (pintype "bidirectional"))
    )
    (net (code "78") (name "ROTENC2_B") (class "Default")
      (node (ref "KNOBBOARD") (pin "7") (pinfunction "7_7") (pintype "passive"))
      (node (ref "TEENSY_3.6") (pin "39/A20") (pinfunction "39/A20_39/A20") (pintype "bidirectional"))
    )
    (net (code "79") (name "ROTENC3_A") (class "Default")
      (node (ref "KNOBBOARD") (pin "2") (pinfunction "2_2") (pintype "passive"))
      (node (ref "TEENSY_3.6") (pin "38/A19") (pinfunction "38/A19_38/A19") (pintype "bidirectional"))
    )
    (net (code "80") (name "ROTENC3_B") (class "Default")
      (node (ref "KNOBBOARD") (pin "4") (pinfunction "4_4") (pintype "passive"))
      (node (ref "TEENSY_3.6") (pin "37/A18") (pinfunction "37/A18_37/A18") (pintype "bidirectional"))
    )
    (net (code "81") (name "ROTENC4_A") (class "Default")
      (node (ref "KNOBBOARD") (pin "6") (pinfunction "6_6") (pintype "passive"))
      (node (ref "TEENSY_3.6") (pin "36/A17") (pinfunction "36/A17_36/A17") (pintype "bidirectional"))
    )
    (net (code "82") (name "ROTENC4_B") (class "Default")
      (node (ref "KNOBBOARD") (pin "8") (pinfunction "8_8") (pintype "passive"))
      (node (ref "TEENSY_3.6") (pin "35/A16") (pinfunction "35/A16_35/A16") (pintype "bidirectional"))
    )
    (net (code "83") (name "R_INPUT1") (class "Default")
      (node (ref "C1") (pin "2") (pinfunction "2_2") (pintype "passive"))
      (node (ref "XPN1") (pin "12") (pinfunction "12_12") (pintype "passive"))
    )
    (net (code "84") (name "R_INPUT2") (class "Default")
      (node (ref "C2") (pin "2") (pinfunction "2_2") (pintype "passive"))
      (node (ref "XPN2") (pin "12") (pinfunction "12_12") (pintype "passive"))
    )
    (net (code "85") (name "R_INPUT3") (class "Default")
      (node (ref "C3") (pin "2") (pinfunction "2_2") (pintype "passive"))
      (node (ref "XPN3") (pin "12") (pinfunction "12_12") (pintype "passive"))
    )
    (net (code "86") (name "R_INPUT4") (class "Default")
      (node (ref "C4") (pin "2") (pinfunction "2_2") (pintype "passive"))
      (node (ref "XPN4") (pin "12") (pinfunction "12_12") (pintype "passive"))
    )
    (net (code "87") (name "R_INPUT5") (class "Default")
      (node (ref "C5") (pin "2") (pinfunction "2_2") (pintype "passive"))
      (node (ref "XPN5") (pin "12") (pinfunction "12_12") (pintype "passive"))
    )
    (net (code "88") (name "R_INPUT6") (class "Default")
      (node (ref "C6") (pin "2") (pinfunction "2_2") (pintype "passive"))
      (node (ref "XPN6") (pin "12") (pinfunction "12_12") (pintype "passive"))
    )
    (net (code "89") (name "R_INPUT7") (class "Default")
      (node (ref "C7") (pin "2") (pinfunction "2_2") (pintype "passive"))
      (node (ref "XPN7") (pin "12") (pinfunction "12_12") (pintype "passive"))
    )
    (net (code "90") (name "R_INPUT8") (class "Default")
      (node (ref "C8") (pin "2") (pinfunction "2_2") (pintype "passive"))
      (node (ref "XPN8") (pin "12") (pinfunction "12_12") (pintype "passive"))
    )
    (net (code "91") (name "SCR_BL") (class "Default")
      (node (ref "SCR") (pin "29") (pinfunction "1_29") (pintype "passive"))
      (node (ref "TEENSY_3.6") (pin "16/A2") (pinfunction "16/A2_16/A2") (pintype "bidirectional"))
    )
    (net (code "92") (name "SCR_CLK") (class "Default")
      (node (ref "SCR") (pin "24") (pinfunction "1_24") (pintype "passive"))
      (node (ref "TEENSY_3.6") (pin "13/SCK") (pinfunction "13/SCK_13/SCK") (pintype "bidirectional"))
    )
    (net (code "93") (name "SCR_CS") (class "Default")
      (node (ref "SCR") (pin "23") (pinfunction "1_23") (pintype "passive"))
      (node (ref "TEENSY_3.6") (pin "10/CS") (pinfunction "10/CS_10/CS") (pintype "bidirectional"))
    )
    (net (code "94") (name "SCR_DC") (class "Default")
      (node (ref "SCR") (pin "25") (pinfunction "1_25") (pintype "passive"))
      (node (ref "TEENSY_3.6") (pin "9/CS") (pinfunction "9/CS_9/CS") (pintype "bidirectional"))
    )
    (net (code "95") (name "SCR_MOSI") (class "Default")
      (node (ref "SCR") (pin "27") (pinfunction "1_27") (pintype "passive"))
      (node (ref "TEENSY_3.6") (pin "11/MOSI") (pinfunction "11/MOSI_11/MOSI") (pintype "bidirectional"))
    )
    (net (code "96") (name "SCR_MOSO") (class "Default")
      (node (ref "SCR") (pin "28") (pinfunction "1_28") (pintype "passive"))
      (node (ref "TEENSY_3.6") (pin "12/MISO") (pinfunction "12/MISO_12/MISO") (pintype "bidirectional"))
    )
    (net (code "97") (name "SDCLK") (class "Default")
      (node (ref "PORTBOARD") (pin "19") (pinfunction "19_19") (pintype "passive"))
      (node (ref "SDPIN5") (pin "1") (pinfunction "P_1") (pintype "passive"))
    )
    (net (code "98") (name "SDCMD") (class "Default")
      (node (ref "PORTBOARD") (pin "20") (pinfunction "20_20") (pintype "passive"))
      (node (ref "SDPIN3") (pin "1") (pinfunction "P_1") (pintype "passive"))
    )
    (net (code "99") (name "SDDATA0") (class "Default")
      (node (ref "PORTBOARD") (pin "15") (pinfunction "15_15") (pintype "passive"))
      (node (ref "SDPIN7") (pin "1") (pinfunction "P_1") (pintype "passive"))
    )
    (net (code "100") (name "SDDATA1") (class "Default")
      (node (ref "PORTBOARD") (pin "16") (pinfunction "16_16") (pintype "passive"))
      (node (ref "SDPIN8") (pin "1") (pinfunction "P_1") (pintype "passive"))
    )
    (net (code "101") (name "SDDATA2") (class "Default")
      (node (ref "PORTBOARD") (pin "17") (pinfunction "17_17") (pintype "passive"))
      (node (ref "SDPIN1") (pin "1") (pinfunction "P_1") (pintype "passive"))
    )
    (net (code "102") (name "SDDATA3") (class "Default")
      (node (ref "PORTBOARD") (pin "18") (pinfunction "18_18") (pintype "passive"))
      (node (ref "SDPIN2") (pin "1") (pinfunction "P_1") (pintype "passive"))
    )
    (net (code "103") (name "TEENSY_L") (class "Default")
      (node (ref "C18") (pin "2") (pinfunction "2_2") (pintype "passive"))
      (node (ref "TEENSY_3.6") (pin "21/DAC0") (pinfunction "A21/DAC0_21/DAC0") (pintype "bidirectional"))
    )
    (net (code "104") (name "TEENSY_R") (class "Default")
      (node (ref "C9") (pin "2") (pinfunction "2_2") (pintype "passive"))
      (node (ref "TEENSY_3.6") (pin "A22/DAC1") (pinfunction "A22/DAC1_A22/DAC1") (pintype "bidirectional"))
    )
    (net (code "105") (name "USBDATA+") (class "Default")
      (node (ref "PORTBOARD") (pin "13") (pinfunction "13_13") (pintype "passive"))
      (node (ref "USBPIN+") (pin "1") (pinfunction "P_1") (pintype "passive"))
    )
    (net (code "106") (name "USBDATA-") (class "Default")
      (node (ref "PORTBOARD") (pin "14") (pinfunction "14_14") (pintype "passive"))
      (node (ref "USBPIN-") (pin "1") (pinfunction "P_1") (pintype "passive"))
    )
    (net (code "107") (name "XPN_CLK") (class "Default")
      (node (ref "TEENSY_3.6") (pin "20/A6") (pinfunction "20/A6_20/A6") (pintype "bidirectional"))
      (node (ref "XPN1") (pin "4") (pinfunction "4_4") (pintype "passive"))
      (node (ref "XPN2") (pin "4") (pinfunction "4_4") (pintype "passive"))
      (node (ref "XPN3") (pin "4") (pinfunction "4_4") (pintype "passive"))
      (node (ref "XPN4") (pin "4") (pinfunction "4_4") (pintype "passive"))
      (node (ref "XPN5") (pin "4") (pinfunction "4_4") (pintype "passive"))
      (node (ref "XPN6") (pin "4") (pinfunction "4_4") (pintype "passive"))
      (node (ref "XPN7") (pin "4") (pinfunction "4_4") (pintype "passive"))
      (node (ref "XPN8") (pin "4") (pinfunction "4_4") (pintype "passive"))
    )
    (net (code "108") (name "XPN_CS1") (class "Default")
      (node (ref "TEENSY_3.6") (pin "6") (pinfunction "6_6") (pintype "bidirectional"))
      (node (ref "XPN1") (pin "10") (pinfunction "10_10") (pintype "passive"))
    )
    (net (code "109") (name "XPN_CS2") (class "Default")
      (node (ref "TEENSY_3.6") (pin "24") (pinfunction "24_24") (pintype "bidirectional"))
      (node (ref "XPN2") (pin "10") (pinfunction "10_10") (pintype "passive"))
    )
    (net (code "110") (name "XPN_CS3") (class "Default")
      (node (ref "TEENSY_3.6") (pin "25") (pinfunction "25_25") (pintype "bidirectional"))
      (node (ref "XPN3") (pin "10") (pinfunction "10_10") (pintype "passive"))
    )
    (net (code "111") (name "XPN_CS4") (class "Default")
      (node (ref "TEENSY_3.6") (pin "26") (pinfunction "26_26") (pintype "bidirectional"))
      (node (ref "XPN4") (pin "10") (pinfunction "10_10") (pintype "passive"))
    )
    (net (code "112") (name "XPN_CS5") (class "Default")
      (node (ref "TEENSY_3.6") (pin "27") (pinfunction "27_27") (pintype "bidirectional"))
      (node (ref "XPN5") (pin "10") (pinfunction "10_10") (pintype "passive"))
    )
    (net (code "113") (name "XPN_CS6") (class "Default")
      (node (ref "TEENSY_3.6") (pin "15/A1") (pinfunction "15/A1_15/A1") (pintype "bidirectional"))
      (node (ref "XPN6") (pin "10") (pinfunction "10_10") (pintype "passive"))
    )
    (net (code "114") (name "XPN_CS7") (class "Default")
      (node (ref "TEENSY_3.6") (pin "14/A0") (pinfunction "14/A0_14/A0") (pintype "bidirectional"))
      (node (ref "XPN7") (pin "10") (pinfunction "10_10") (pintype "passive"))
    )
    (net (code "115") (name "XPN_CS8") (class "Default")
      (node (ref "TEENSY_3.6") (pin "22/A8") (pinfunction "22/A8_22/A8") (pintype "bidirectional"))
      (node (ref "XPN8") (pin "10") (pinfunction "10_10") (pintype "passive"))
    )
    (net (code "116") (name "XPN_MISO") (class "Default")
      (node (ref "TEENSY_3.6") (pin "5") (pinfunction "5_5") (pintype "bidirectional"))
      (node (ref "XPN1") (pin "8") (pinfunction "8_8") (pintype "passive"))
      (node (ref "XPN2") (pin "8") (pinfunction "8_8") (pintype "passive"))
      (node (ref "XPN3") (pin "8") (pinfunction "8_8") (pintype "passive"))
      (node (ref "XPN4") (pin "8") (pinfunction "8_8") (pintype "passive"))
      (node (ref "XPN5") (pin "8") (pinfunction "8_8") (pintype "passive"))
      (node (ref "XPN6") (pin "8") (pinfunction "8_8") (pintype "passive"))
      (node (ref "XPN7") (pin "8") (pinfunction "8_8") (pintype "passive"))
      (node (ref "XPN8") (pin "8") (pinfunction "8_8") (pintype "passive"))
    )
    (net (code "117") (name "XPN_MOSI") (class "Default")
      (node (ref "TEENSY_3.6") (pin "21/A7") (pinfunction "21/A7_21/A7") (pintype "bidirectional"))
      (node (ref "XPN1") (pin "6") (pinfunction "6_6") (pintype "passive"))
      (node (ref "XPN2") (pin "6") (pinfunction "6_6") (pintype "passive"))
      (node (ref "XPN3") (pin "6") (pinfunction "6_6") (pintype "passive"))
      (node (ref "XPN4") (pin "6") (pinfunction "6_6") (pintype "passive"))
      (node (ref "XPN5") (pin "6") (pinfunction "6_6") (pintype "passive"))
      (node (ref "XPN6") (pin "6") (pinfunction "6_6") (pintype "passive"))
      (node (ref "XPN7") (pin "6") (pinfunction "6_6") (pintype "passive"))
      (node (ref "XPN8") (pin "6") (pinfunction "6_6") (pintype "passive"))
    )
    (net (code "118") (name "unconnected-(BUTTONS-Pad8)") (class "Default")
      (node (ref "BUTTONS") (pin "8") (pinfunction "8_8") (pintype "passive"))
    )
    (net (code "119") (name "unconnected-(J1-Pad2)") (class "Default")
      (node (ref "J1") (pin "2") (pinfunction "2_2") (pintype "passive"))
    )
    (net (code "120") (name "unconnected-(J2-Pad2)") (class "Default")
      (node (ref "J2") (pin "2") (pinfunction "2_2") (pintype "passive"))
    )
    (net (code "121") (name "unconnected-(KNOBBOARD-Pad12)") (class "Default")
      (node (ref "KNOBBOARD") (pin "12") (pinfunction "12_12") (pintype "passive"))
    )
    (net (code "122") (name "unconnected-(PORTBOARD-Pad21)") (class "Default")
      (node (ref "PORTBOARD") (pin "21") (pinfunction "21_21") (pintype "passive"))
    )
    (net (code "123") (name "unconnected-(PORTBOARD-Pad22)") (class "Default")
      (node (ref "PORTBOARD") (pin "22") (pinfunction "22_22") (pintype "passive"))
    )
    (net (code "124") (name "unconnected-(SCRAA-1-Pad33)") (class "Default")
      (node (ref "SCR") (pin "33") (pinfunction "1_33") (pintype "passive"))
    )
    (net (code "125") (name "unconnected-(SCRAB-1-Pad34)") (class "Default")
      (node (ref "SCR") (pin "34") (pinfunction "1_34") (pintype "passive"))
    )
    (net (code "126") (name "unconnected-(SCRAC-1-Pad35)") (class "Default")
      (node (ref "SCR") (pin "35") (pinfunction "1_35") (pintype "passive"))
    )
    (net (code "127") (name "unconnected-(SCRAD-1-Pad36)") (class "Default")
      (node (ref "SCR") (pin "36") (pinfunction "1_36") (pintype "passive"))
    )
    (net (code "128") (name "unconnected-(SCRAE-1-Pad37)") (class "Default")
      (node (ref "SCR") (pin "37") (pinfunction "1_37") (pintype "passive"))
    )
    (net (code "129") (name "unconnected-(SCRAF-1-Pad38)") (class "Default")
      (node (ref "SCR") (pin "38") (pinfunction "1_38") (pintype "passive"))
    )
    (net (code "130") (name "unconnected-(SCRAG-1-Pad39)") (class "Default")
      (node (ref "SCR") (pin "39") (pinfunction "1_39") (pintype "passive"))
    )
    (net (code "131") (name "unconnected-(SCRAH-1-Pad4)") (class "Default")
      (node (ref "SCR") (pin "4") (pinfunction "1_4") (pintype "passive"))
    )
    (net (code "132") (name "unconnected-(SCRAI-1-Pad40)") (class "Default")
      (node (ref "SCR") (pin "40") (pinfunction "1_40") (pintype "passive"))
    )
    (net (code "133") (name "unconnected-(SCRAJ-1-Pad5)") (class "Default")
      (node (ref "SCR") (pin "5") (pinfunction "1_5") (pintype "passive"))
    )
    (net (code "134") (name "unconnected-(SCRAK-1-Pad6)") (class "Default")
      (node (ref "SCR") (pin "6") (pinfunction "1_6") (pintype "passive"))
    )
    (net (code "135") (name "unconnected-(SCRAL-1-Pad7)") (class "Default")
      (node (ref "SCR") (pin "7") (pinfunction "1_7") (pintype "passive"))
    )
    (net (code "136") (name "unconnected-(SCRAM-1-Pad8)") (class "Default")
      (node (ref "SCR") (pin "8") (pinfunction "1_8") (pintype "passive"))
    )
    (net (code "137") (name "unconnected-(SCRAN-1-Pad9)") (class "Default")
      (node (ref "SCR") (pin "9") (pinfunction "1_9") (pintype "passive"))
    )
    (net (code "138") (name "unconnected-(SCRB-1-Pad10)") (class "Default")
      (node (ref "SCR") (pin "10") (pinfunction "1_10") (pintype "passive"))
    )
    (net (code "139") (name "unconnected-(SCRC-1-Pad11)") (class "Default")
      (node (ref "SCR") (pin "11") (pinfunction "1_11") (pintype "passive"))
    )
    (net (code "140") (name "unconnected-(SCRD-1-Pad12)") (class "Default")
      (node (ref "SCR") (pin "12") (pinfunction "1_12") (pintype "passive"))
    )
    (net (code "141") (name "unconnected-(SCRE-1-Pad13)") (class "Default")
      (node (ref "SCR") (pin "13") (pinfunction "1_13") (pintype "passive"))
    )
    (net (code "142") (name "unconnected-(SCRF-1-Pad14)") (class "Default")
      (node (ref "SCR") (pin "14") (pinfunction "1_14") (pintype "passive"))
    )
    (net (code "143") (name "unconnected-(SCRG-1-Pad15)") (class "Default")
      (node (ref "SCR") (pin "15") (pinfunction "1_15") (pintype "passive"))
    )
    (net (code "144") (name "unconnected-(SCRH-1-Pad16)") (class "Default")
      (node (ref "SCR") (pin "16") (pinfunction "1_16") (pintype "passive"))
    )
    (net (code "145") (name "unconnected-(SCRI-1-Pad17)") (class "Default")
      (node (ref "SCR") (pin "17") (pinfunction "1_17") (pintype "passive"))
    )
    (net (code "146") (name "unconnected-(SCRJ-1-Pad18)") (class "Default")
      (node (ref "SCR") (pin "18") (pinfunction "1_18") (pintype "passive"))
    )
    (net (code "147") (name "unconnected-(SCRK-1-Pad19)") (class "Default")
      (node (ref "SCR") (pin "19") (pinfunction "1_19") (pintype "passive"))
    )
    (net (code "148") (name "unconnected-(SCRM-1-Pad20)") (class "Default")
      (node (ref "SCR") (pin "20") (pinfunction "1_20") (pintype "passive"))
    )
    (net (code "149") (name "unconnected-(SCRN-1-Pad21)") (class "Default")
      (node (ref "SCR") (pin "21") (pinfunction "1_21") (pintype "passive"))
    )
    (net (code "150") (name "unconnected-(SCRO-1-Pad22)") (class "Default")
      (node (ref "SCR") (pin "22") (pinfunction "1_22") (pintype "passive"))
    )
    (net (code "151") (name "unconnected-(SCRS-1-Pad26)") (class "Default")
      (node (ref "SCR") (pin "26") (pinfunction "1_26") (pintype "passive"))
    )
    (net (code "152") (name "unconnected-(SCRW-1-Pad3)") (class "Default")
      (node (ref "SCR") (pin "3") (pinfunction "1_3") (pintype "passive"))
    )
    (net (code "153") (name "unconnected-(SCRX-1-Pad30)") (class "Default")
      (node (ref "SCR") (pin "30") (pinfunction "1_30") (pintype "passive"))
    )
    (net (code "154") (name "unconnected-(SCRY-1-Pad31)") (class "Default")
      (node (ref "SCR") (pin "31") (pinfunction "1_31") (pintype "passive"))
    )
    (net (code "155") (name "unconnected-(SCRZ-1-Pad32)") (class "Default")
      (node (ref "SCR") (pin "32") (pinfunction "1_32") (pintype "passive"))
    )
    (net (code "156") (name "unconnected-(TEENSY_3.6-Pad3V3_2)") (class "Default")
      (node (ref "TEENSY_3.6") (pin "3V3_2") (pinfunction "3V3_2_3V3_2") (pintype "bidirectional"))
    )
    (net (code "157") (name "unconnected-(TEENSY_3.6-Pad3V3_LO)") (class "Default")
      (node (ref "TEENSY_3.6") (pin "3V3_LO") (pinfunction "3V3_LO_3V3_LO") (pintype "bidirectional"))
    )
    (net (code "158") (name "unconnected-(TEENSY_3.6-PadA11)") (class "Default")
      (node (ref "TEENSY_3.6") (pin "A11") (pinfunction "A11_A11") (pintype "bidirectional"))
    )
    (net (code "159") (name "unconnected-(TEENSY_3.6-PadAGND)") (class "Default")
      (node (ref "TEENSY_3.6") (pin "AGND") (pinfunction "AGND_AGND") (pintype "bidirectional"))
    )
    (net (code "160") (name "unconnected-(TEENSY_3.6-PadAREF)") (class "Default")
      (node (ref "TEENSY_3.6") (pin "AREF") (pinfunction "AREF_AREF") (pintype "bidirectional"))
    )
    (net (code "161") (name "unconnected-(TEENSY_3.6-PadGND2)") (class "Default")
      (node (ref "TEENSY_3.6") (pin "GND2") (pinfunction "GND2_GND2") (pintype "bidirectional"))
    )
    (net (code "162") (name "unconnected-(TEENSY_3.6-PadGND3)") (class "Default")
      (node (ref "TEENSY_3.6") (pin "GND3") (pinfunction "GND3_GND3") (pintype "bidirectional"))
    )
    (net (code "163") (name "unconnected-(TEENSY_3.6-PadPROG)") (class "Default")
      (node (ref "TEENSY_3.6") (pin "PROG") (pinfunction "PROG_PROG") (pintype "bidirectional"))
    )
    (net (code "164") (name "unconnected-(TEENSY_3.6-PadRESET)") (class "Default")
      (node (ref "TEENSY_3.6") (pin "RESET") (pinfunction "RESET_RESET") (pintype "bidirectional"))
    )
    (net (code "165") (name "unconnected-(TEENSY_3.6-PadU5V)") (class "Default")
      (node (ref "TEENSY_3.6") (pin "U5V") (pinfunction "U5V_U5V") (pintype "bidirectional"))
    )
    (net (code "166") (name "unconnected-(TEENSY_3.6-PadUD+)") (class "Default")
      (node (ref "TEENSY_3.6") (pin "UD+") (pinfunction "UD+_UD+") (pintype "bidirectional"))
    )
    (net (code "167") (name "unconnected-(TEENSY_3.6-PadUD-)") (class "Default")
      (node (ref "TEENSY_3.6") (pin "UD-") (pinfunction "UD-_UD-") (pintype "bidirectional"))
    )
    (net (code "168") (name "unconnected-(TEENSY_3.6-PadUGND1)") (class "Default")
      (node (ref "TEENSY_3.6") (pin "UGND1") (pinfunction "UGND1_UGND1") (pintype "bidirectional"))
    )
    (net (code "169") (name "unconnected-(TEENSY_3.6-PadUGND2)") (class "Default")
      (node (ref "TEENSY_3.6") (pin "UGND2") (pinfunction "UGND2_UGND2") (pintype "bidirectional"))
    )
    (net (code "170") (name "unconnected-(TEENSY_3.6-PadVBAT)") (class "Default")
      (node (ref "TEENSY_3.6") (pin "VBAT") (pinfunction "VBAT_VBAT") (pintype "bidirectional"))
    )
    (net (code "171") (name "unconnected-(TEENSY_3.6-PadVUSB)") (class "Default")
      (node (ref "TEENSY_3.6") (pin "VUSB") (pinfunction "VUSB_VUSB") (pintype "bidirectional"))
    )
    (net (code "172") (name "unconnected-(XPN1-Pad2)") (class "Default")
      (node (ref "XPN1") (pin "2") (pinfunction "2_2") (pintype "passive"))
    )
    (net (code "173") (name "unconnected-(XPN2-Pad2)") (class "Default")
      (node (ref "XPN2") (pin "2") (pinfunction "2_2") (pintype "passive"))
    )
    (net (code "174") (name "unconnected-(XPN3-Pad2)") (class "Default")
      (node (ref "XPN3") (pin "2") (pinfunction "2_2") (pintype "passive"))
    )
    (net (code "175") (name "unconnected-(XPN4-Pad2)") (class "Default")
      (node (ref "XPN4") (pin "2") (pinfunction "2_2") (pintype "passive"))
    )
    (net (code "176") (name "unconnected-(XPN5-Pad2)") (class "Default")
      (node (ref "XPN5") (pin "2") (pinfunction "2_2") (pintype "passive"))
    )
    (net (code "177") (name "unconnected-(XPN6-Pad2)") (class "Default")
      (node (ref "XPN6") (pin "2") (pinfunction "2_2") (pintype "passive"))
    )
    (net (code "178") (name "unconnected-(XPN7-Pad2)") (class "Default")
      (node (ref "XPN7") (pin "2") (pinfunction "2_2") (pintype "passive"))
    )
    (net (code "179") (name "unconnected-(XPN8-Pad2)") (class "Default")
      (node (ref "XPN8") (pin "2") (pinfunction "2_2") (pintype "passive"))
    )
  )
)
